# PTI.net
KiCad netlist of a schematic drawn in EAGLE
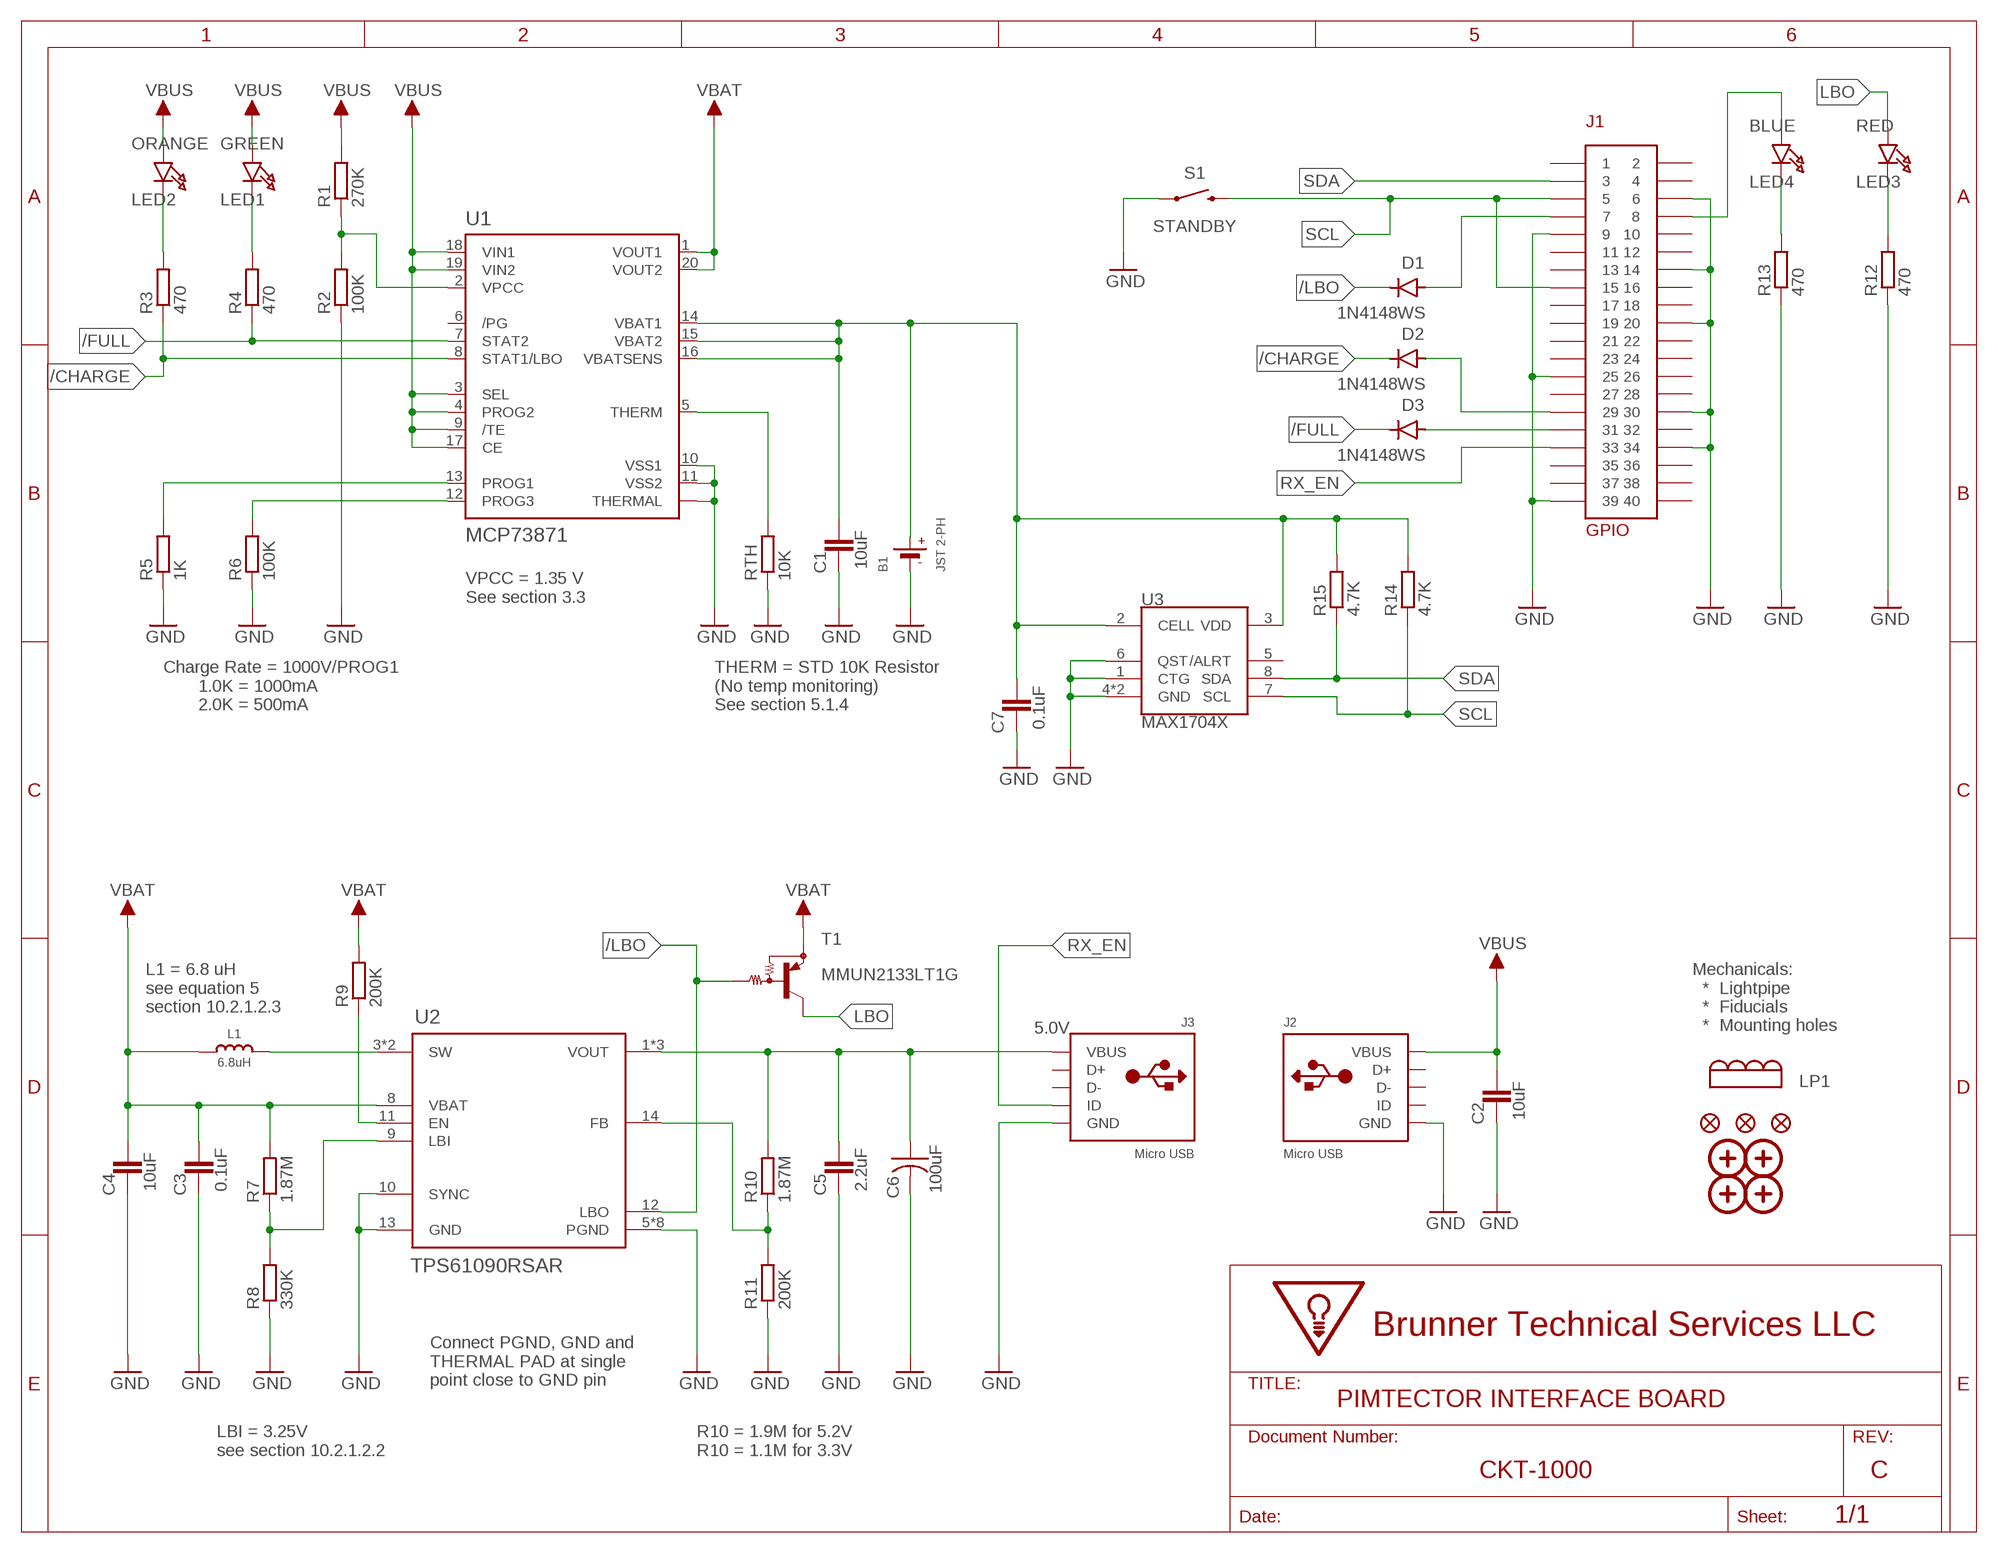
[diagram p0: schematic, sheet 1]

(export (version "E")
  (design (tool "Eeschema 10.0.6"))
  (components
    (comp (ref "B1")
      (value "JST 2-PH")
      (footprint "eagle-import:JSTPH2")
      (libsource (lib "eagle-import") (part "BATTERY"))
    )
    (comp (ref "C1")
      (value "10uF")
      (footprint "eagle-import:C0805")
      (libsource (lib "eagle-import") (part "C-EUC0805"))
    )
    (comp (ref "C2")
      (value "10uF")
      (footprint "eagle-import:C0805")
      (libsource (lib "eagle-import") (part "C-EUC0805"))
    )
    (comp (ref "C3")
      (value "0.1uF")
      (footprint "eagle-import:C0805")
      (libsource (lib "eagle-import") (part "C-EUC0805"))
    )
    (comp (ref "C4")
      (value "10uF")
      (footprint "eagle-import:C0805")
      (libsource (lib "eagle-import") (part "C-EUC0805"))
    )
    (comp (ref "C5")
      (value "2.2uF")
      (footprint "eagle-import:C0805")
      (libsource (lib "eagle-import") (part "C-EUC0805"))
    )
    (comp (ref "C6")
      (value "100uF")
      (footprint "eagle-import:C1210")
      (libsource (lib "eagle-import") (part "C-USC1210"))
    )
    (comp (ref "C7")
      (value "0.1uF")
      (footprint "eagle-import:C0805")
      (libsource (lib "eagle-import") (part "C-EUC0805"))
    )
    (comp (ref "D1")
      (value "1N4148WS")
      (footprint "eagle-import:SOD-323")
      (fields
        (field (name "DIGIKEY_PART_NUMBER") "1N4148WSFSTR-ND")
        (field (name "MANUFACTURER") "Diodes Incorporated")
        (field (name "CREATED_BY") "PCBLayout.com")
      )
      (libsource (lib "eagle-import") (part "1N4148WS"))
    )
    (comp (ref "D2")
      (value "1N4148WS")
      (footprint "eagle-import:SOD-323")
      (fields
        (field (name "DIGIKEY_PART_NUMBER") "1N4148WSFSTR-ND")
        (field (name "MANUFACTURER") "Diodes Incorporated")
        (field (name "CREATED_BY") "PCBLayout.com")
      )
      (libsource (lib "eagle-import") (part "1N4148WS"))
    )
    (comp (ref "D3")
      (value "1N4148WS")
      (footprint "eagle-import:SOD-323")
      (fields
        (field (name "DIGIKEY_PART_NUMBER") "1N4148WSFSTR-ND")
        (field (name "MANUFACTURER") "Diodes Incorporated")
        (field (name "CREATED_BY") "PCBLayout.com")
      )
      (libsource (lib "eagle-import") (part "1N4148WS"))
    )
    (comp (ref "FID1")
      (value "FIDUCIAL\"\"")
      (footprint "eagle-import:FIDUCIAL_1MM")
      (libsource (lib "eagle-import") (part "FIDUCIAL{dblquote}{dblquote}"))
    )
    (comp (ref "FID2")
      (value "FIDUCIAL\"\"")
      (footprint "eagle-import:FIDUCIAL_1MM")
      (libsource (lib "eagle-import") (part "FIDUCIAL{dblquote}{dblquote}"))
    )
    (comp (ref "FID3")
      (value "FIDUCIAL\"\"")
      (footprint "eagle-import:FIDUCIAL_1MM")
      (libsource (lib "eagle-import") (part "FIDUCIAL{dblquote}{dblquote}"))
    )
    (comp (ref "J1")
      (value "GPIO")
      (footprint "eagle-import:HEADER-FE-2X20-TH")
      (libsource (lib "eagle-import") (part "HEADER-FE-2X20THRU-HOLE"))
    )
    (comp (ref "J2")
      (value "Micro USB")
      (footprint "eagle-import:AMPHENOL_10103594")
      (libsource (lib "eagle-import") (part "USB"))
    )
    (comp (ref "J3")
      (value "Micro USB")
      (footprint "eagle-import:AMPHENOL_10103594")
      (libsource (lib "eagle-import") (part "USB"))
    )
    (comp (ref "L1")
      (value "6.8uH")
      (footprint "eagle-import:INDUCTOR_5X5MM_TDK_VLC5045")
      (libsource (lib "eagle-import") (part "INDUCTORTDK_VLC5045"))
    )
    (comp (ref "LED1")
      (value "GREEN")
      (footprint "eagle-import:CHIPLED_0805_NOOUTLINE")
      (libsource (lib "eagle-import") (part "LED0805_NOOUTLINE"))
    )
    (comp (ref "LED2")
      (value "ORANGE")
      (footprint "eagle-import:CHIPLED_0805_NOOUTLINE")
      (libsource (lib "eagle-import") (part "LED0805_NOOUTLINE"))
    )
    (comp (ref "LED3")
      (value "RED")
      (footprint "eagle-import:CHIPLED_0805_NOOUTLINE")
      (libsource (lib "eagle-import") (part "LED0805_NOOUTLINE"))
    )
    (comp (ref "LED4")
      (value "BLUE")
      (footprint "eagle-import:CHIPLED_0805_NOOUTLINE")
      (libsource (lib "eagle-import") (part "LED0805_NOOUTLINE"))
    )
    (comp (ref "LP1")
      (value "LIGHTPIPE")
      (footprint "eagle-import:LIGHTPIPE_QUAD_VERT_3MM")
      (libsource (lib "eagle-import") (part "LIGHTPIPE"))
    )
    (comp (ref "MH1")
      (value "MOUNTING-HOLES")
      (footprint "eagle-import:MOUNTING-HOLE-2.75X3MM")
      (libsource (lib "eagle-import") (part "MOUNTING-HOLES"))
    )
    (comp (ref "MH2")
      (value "MOUNTING-HOLES")
      (footprint "eagle-import:MOUNTING-HOLE-2.75X3MM")
      (libsource (lib "eagle-import") (part "MOUNTING-HOLES"))
    )
    (comp (ref "MH3")
      (value "MOUNTING-HOLES")
      (footprint "eagle-import:MOUNTING-HOLE-2.75X3MM")
      (libsource (lib "eagle-import") (part "MOUNTING-HOLES"))
    )
    (comp (ref "MH4")
      (value "MOUNTING-HOLES")
      (footprint "eagle-import:MOUNTING-HOLE-2.75X3MM")
      (libsource (lib "eagle-import") (part "MOUNTING-HOLES"))
    )
    (comp (ref "R1")
      (value "270K")
      (footprint "eagle-import:R0805")
      (libsource (lib "eagle-import") (part "R-EU_R0805"))
    )
    (comp (ref "R2")
      (value "100K")
      (footprint "eagle-import:R0805")
      (libsource (lib "eagle-import") (part "R-EU_R0805"))
    )
    (comp (ref "R3")
      (value "470")
      (footprint "eagle-import:R0805")
      (libsource (lib "eagle-import") (part "R-EU_R0805"))
    )
    (comp (ref "R4")
      (value "470")
      (footprint "eagle-import:R0805")
      (libsource (lib "eagle-import") (part "R-EU_R0805"))
    )
    (comp (ref "R5")
      (value "1K")
      (footprint "eagle-import:R0805")
      (libsource (lib "eagle-import") (part "R-EU_R0805"))
    )
    (comp (ref "R6")
      (value "100K")
      (footprint "eagle-import:R0805")
      (libsource (lib "eagle-import") (part "R-EU_R0805"))
    )
    (comp (ref "R7")
      (value "1.87M")
      (footprint "eagle-import:R0805")
      (libsource (lib "eagle-import") (part "R-EU_R0805"))
    )
    (comp (ref "R8")
      (value "330K")
      (footprint "eagle-import:R0805")
      (libsource (lib "eagle-import") (part "R-EU_R0805"))
    )
    (comp (ref "R9")
      (value "200K")
      (footprint "eagle-import:R0805")
      (libsource (lib "eagle-import") (part "R-EU_R0805"))
    )
    (comp (ref "R10")
      (value "1.87M")
      (footprint "eagle-import:R0805")
      (libsource (lib "eagle-import") (part "R-EU_R0805"))
    )
    (comp (ref "R11")
      (value "200K")
      (footprint "eagle-import:R0805")
      (libsource (lib "eagle-import") (part "R-EU_R0805"))
    )
    (comp (ref "R12")
      (value "470")
      (footprint "eagle-import:R0805")
      (libsource (lib "eagle-import") (part "R-EU_R0805"))
    )
    (comp (ref "R13")
      (value "470")
      (footprint "eagle-import:R0805")
      (libsource (lib "eagle-import") (part "R-EU_R0805"))
    )
    (comp (ref "R14")
      (value "4.7K")
      (footprint "eagle-import:R0805")
      (libsource (lib "eagle-import") (part "R-EU_R0805"))
    )
    (comp (ref "R15")
      (value "4.7K")
      (footprint "eagle-import:R0805")
      (libsource (lib "eagle-import") (part "R-EU_R0805"))
    )
    (comp (ref "RTH")
      (value "10K")
      (footprint "eagle-import:R0805")
      (libsource (lib "eagle-import") (part "R-EU_R0805"))
    )
    (comp (ref "S1")
      (value "STANDBY")
      (footprint "eagle-import:TACTILE_SWITCH_PTH_12MM")
      (libsource (lib "eagle-import") (part "MOMENTARY-SWITCH-SPST-PTH-12MM"))
    )
    (comp (ref "T1")
      (value "MMUN2133LT1G")
      (footprint "eagle-import:SC59-BEC")
      (libsource (lib "eagle-import") (part "-PNP_DRIVER-SC59-BECMUN2111T1"))
    )
    (comp (ref "U1")
      (value "MCP73871")
      (footprint "eagle-import:QFN20_4MM")
      (libsource (lib "eagle-import") (part "MCP73871"))
    )
    (comp (ref "U2")
      (value "TPS61090RSAR")
      (footprint "eagle-import:RSA16_4MMX4MM_VQFN")
      (fields (field (name "MANUFACTURER") "TI"))
      (libsource (lib "eagle-import") (part "TPS6109X"))
    )
    (comp (ref "U3")
      (value "MAX1704X")
      (footprint "eagle-import:TDFN-8")
      (libsource (lib "eagle-import") (part "MAX1704X"))
    )
  )
  (nets
    (net (code "1") (name "/5.0V") (class "Default")
      (node (ref "C5") (pin "1") (pinfunction "1_1") (pintype "passive"))
      (node (ref "C6") (pin "1") (pinfunction "1_1") (pintype "passive"))
      (node (ref "J3") (pin "VBUS") (pinfunction "VBUS_VBUS") (pintype "power_in"))
      (node (ref "R10") (pin "2") (pinfunction "2_2") (pintype "passive"))
      (node (ref "U2") (pin "1") (pinfunction "VOUT_1") (pintype "output"))
      (node (ref "U2") (pin "15") (pinfunction "VOUT_15") (pintype "output"))
      (node (ref "U2") (pin "16") (pinfunction "VOUT_16") (pintype "output"))
    )
    (net (code "2") (name "GND") (class "Default")
      (node (ref "B1") (pin "1") (pinfunction "-_1") (pintype "passive"))
      (node (ref "B1") (pin "NC1") (pinfunction "-_NC1") (pintype "passive"))
      (node (ref "B1") (pin "NC2") (pinfunction "-_NC2") (pintype "passive"))
      (node (ref "C1") (pin "2") (pinfunction "2_2") (pintype "passive"))
      (node (ref "C2") (pin "2") (pinfunction "2_2") (pintype "passive"))
      (node (ref "C3") (pin "2") (pinfunction "2_2") (pintype "passive"))
      (node (ref "C4") (pin "2") (pinfunction "2_2") (pintype "passive"))
      (node (ref "C5") (pin "2") (pinfunction "2_2") (pintype "passive"))
      (node (ref "C6") (pin "2") (pinfunction "2_2") (pintype "passive"))
      (node (ref "C7") (pin "2") (pinfunction "2_2") (pintype "passive"))
      (node (ref "J1") (pin "P$14") (pinfunction "14_P$14") (pintype "bidirectional"))
      (node (ref "J1") (pin "P$20") (pinfunction "20_P$20") (pintype "bidirectional"))
      (node (ref "J1") (pin "P$25") (pinfunction "25_P$25") (pintype "bidirectional"))
      (node (ref "J1") (pin "P$30") (pinfunction "30_P$30") (pintype "bidirectional"))
      (node (ref "J1") (pin "P$34") (pinfunction "34_P$34") (pintype "bidirectional"))
      (node (ref "J1") (pin "P$39") (pinfunction "39_P$39") (pintype "bidirectional"))
      (node (ref "J1") (pin "P$6") (pinfunction "6_P$6") (pintype "bidirectional"))
      (node (ref "J1") (pin "P$9") (pinfunction "9_P$9") (pintype "bidirectional"))
      (node (ref "J2") (pin "BASE@1") (pinfunction "GND_BASE@1") (pintype "power_in"))
      (node (ref "J2") (pin "BASE@2") (pinfunction "GND_BASE@2") (pintype "power_in"))
      (node (ref "J2") (pin "GND") (pinfunction "GND_GND") (pintype "power_in"))
      (node (ref "J2") (pin "SPRT@1") (pinfunction "GND_SPRT@1") (pintype "power_in"))
      (node (ref "J2") (pin "SPRT@2") (pinfunction "GND_SPRT@2") (pintype "power_in"))
      (node (ref "J2") (pin "SPRT@3") (pinfunction "GND_SPRT@3") (pintype "power_in"))
      (node (ref "J2") (pin "SPRT@4") (pinfunction "GND_SPRT@4") (pintype "power_in"))
      (node (ref "J3") (pin "BASE@1") (pinfunction "GND_BASE@1") (pintype "power_in"))
      (node (ref "J3") (pin "BASE@2") (pinfunction "GND_BASE@2") (pintype "power_in"))
      (node (ref "J3") (pin "GND") (pinfunction "GND_GND") (pintype "power_in"))
      (node (ref "J3") (pin "SPRT@1") (pinfunction "GND_SPRT@1") (pintype "power_in"))
      (node (ref "J3") (pin "SPRT@2") (pinfunction "GND_SPRT@2") (pintype "power_in"))
      (node (ref "J3") (pin "SPRT@3") (pinfunction "GND_SPRT@3") (pintype "power_in"))
      (node (ref "J3") (pin "SPRT@4") (pinfunction "GND_SPRT@4") (pintype "power_in"))
      (node (ref "R11") (pin "1") (pinfunction "1_1") (pintype "passive"))
      (node (ref "R12") (pin "1") (pinfunction "1_1") (pintype "passive"))
      (node (ref "R13") (pin "1") (pinfunction "1_1") (pintype "passive"))
      (node (ref "R2") (pin "1") (pinfunction "1_1") (pintype "passive"))
      (node (ref "R5") (pin "1") (pinfunction "1_1") (pintype "passive"))
      (node (ref "R6") (pin "1") (pinfunction "1_1") (pintype "passive"))
      (node (ref "R8") (pin "1") (pinfunction "1_1") (pintype "passive"))
      (node (ref "RTH") (pin "1") (pinfunction "1_1") (pintype "passive"))
      (node (ref "S1") (pin "1") (pinfunction "1_1") (pintype "passive"))
      (node (ref "U1") (pin "10") (pinfunction "VSS1_10") (pintype "bidirectional"))
      (node (ref "U1") (pin "11") (pinfunction "VSS2_11") (pintype "bidirectional"))
      (node (ref "U1") (pin "P$21") (pinfunction "THERMAL_P$21") (pintype "bidirectional"))
      (node (ref "U1") (pin "P$22") (pinfunction "THERMAL_P$22") (pintype "bidirectional"))
      (node (ref "U1") (pin "P$23") (pinfunction "THERMAL_P$23") (pintype "bidirectional"))
      (node (ref "U1") (pin "P$24") (pinfunction "THERMAL_P$24") (pintype "bidirectional"))
      (node (ref "U2") (pin "10") (pinfunction "SYNC_10") (pintype "input"))
      (node (ref "U2") (pin "13") (pinfunction "GND_13") (pintype "power_in"))
      (node (ref "U2") (pin "5") (pinfunction "PGND_5") (pintype "bidirectional"))
      (node (ref "U2") (pin "6") (pinfunction "PGND_6") (pintype "bidirectional"))
      (node (ref "U2") (pin "7") (pinfunction "PGND_7") (pintype "bidirectional"))
      (node (ref "U2") (pin "P$17") (pinfunction "PGND_P$17") (pintype "bidirectional"))
      (node (ref "U2") (pin "P$18") (pinfunction "PGND_P$18") (pintype "bidirectional"))
      (node (ref "U2") (pin "P$19") (pinfunction "PGND_P$19") (pintype "bidirectional"))
      (node (ref "U2") (pin "P$20") (pinfunction "PGND_P$20") (pintype "bidirectional"))
      (node (ref "U2") (pin "P$21") (pinfunction "PGND_P$21") (pintype "bidirectional"))
      (node (ref "U3") (pin "1") (pinfunction "CTG_1") (pintype "bidirectional"))
      (node (ref "U3") (pin "4") (pinfunction "GND_4") (pintype "bidirectional"))
      (node (ref "U3") (pin "6") (pinfunction "QST_6") (pintype "bidirectional"))
      (node (ref "U3") (pin "EP") (pinfunction "GND_EP") (pintype "bidirectional"))
    )
    (net (code "3") (name "LBO") (class "Default")
      (node (ref "LED3") (pin "A") (pinfunction "A_A") (pintype "passive"))
      (node (ref "T1") (pin "C") (pinfunction "C_C") (pintype "passive"))
    )
    (net (code "4") (name "Net-(B1-+)") (class "Default")
      (node (ref "B1") (pin "2") (pinfunction "+_2") (pintype "passive"))
      (node (ref "C1") (pin "1") (pinfunction "1_1") (pintype "passive"))
      (node (ref "C7") (pin "1") (pinfunction "1_1") (pintype "passive"))
      (node (ref "R14") (pin "2") (pinfunction "2_2") (pintype "passive"))
      (node (ref "R15") (pin "2") (pinfunction "2_2") (pintype "passive"))
      (node (ref "U1") (pin "14") (pinfunction "VBAT1_14") (pintype "bidirectional"))
      (node (ref "U1") (pin "15") (pinfunction "VBAT2_15") (pintype "bidirectional"))
      (node (ref "U1") (pin "16") (pinfunction "VBATSENS_16") (pintype "bidirectional"))
      (node (ref "U3") (pin "2") (pinfunction "CELL_2") (pintype "bidirectional"))
      (node (ref "U3") (pin "3") (pinfunction "VDD_3") (pintype "bidirectional"))
    )
    (net (code "5") (name "Net-(J1-7)") (class "Default")
      (node (ref "D1") (pin "A") (pinfunction "A_A") (pintype "passive"))
      (node (ref "J1") (pin "P$7") (pinfunction "7_P$7") (pintype "bidirectional"))
    )
    (net (code "6") (name "Net-(J1-8)") (class "Default")
      (node (ref "J1") (pin "P$8") (pinfunction "8_P$8") (pintype "bidirectional"))
      (node (ref "LED4") (pin "A") (pinfunction "A_A") (pintype "passive"))
    )
    (net (code "7") (name "Net-(J1-29)") (class "Default")
      (node (ref "D2") (pin "A") (pinfunction "A_A") (pintype "passive"))
      (node (ref "J1") (pin "P$29") (pinfunction "29_P$29") (pintype "bidirectional"))
    )
    (net (code "8") (name "Net-(J1-31)") (class "Default")
      (node (ref "D3") (pin "A") (pinfunction "A_A") (pintype "passive"))
      (node (ref "J1") (pin "P$31") (pinfunction "31_P$31") (pintype "bidirectional"))
    )
    (net (code "9") (name "Net-(L1-2)") (class "Default")
      (node (ref "L1") (pin "P$2") (pinfunction "2_P$2") (pintype "passive"))
      (node (ref "U2") (pin "3") (pinfunction "SW_3") (pintype "input"))
      (node (ref "U2") (pin "4") (pinfunction "SW_4") (pintype "input"))
    )
    (net (code "10") (name "Net-(LED1-PadC)") (class "Default")
      (node (ref "LED1") (pin "C") (pinfunction "C_C") (pintype "passive"))
      (node (ref "R4") (pin "2") (pinfunction "2_2") (pintype "passive"))
    )
    (net (code "11") (name "Net-(LED2-PadC)") (class "Default")
      (node (ref "LED2") (pin "C") (pinfunction "C_C") (pintype "passive"))
      (node (ref "R3") (pin "2") (pinfunction "2_2") (pintype "passive"))
    )
    (net (code "12") (name "Net-(LED3-PadC)") (class "Default")
      (node (ref "LED3") (pin "C") (pinfunction "C_C") (pintype "passive"))
      (node (ref "R12") (pin "2") (pinfunction "2_2") (pintype "passive"))
    )
    (net (code "13") (name "Net-(LED4-PadC)") (class "Default")
      (node (ref "LED4") (pin "C") (pinfunction "C_C") (pintype "passive"))
      (node (ref "R13") (pin "2") (pinfunction "2_2") (pintype "passive"))
    )
    (net (code "14") (name "Net-(U1-PROG1)") (class "Default")
      (node (ref "R5") (pin "2") (pinfunction "2_2") (pintype "passive"))
      (node (ref "U1") (pin "13") (pinfunction "PROG1_13") (pintype "bidirectional"))
    )
    (net (code "15") (name "Net-(U1-PROG3)") (class "Default")
      (node (ref "R6") (pin "2") (pinfunction "2_2") (pintype "passive"))
      (node (ref "U1") (pin "12") (pinfunction "PROG3_12") (pintype "bidirectional"))
    )
    (net (code "16") (name "Net-(U1-THERM)") (class "Default")
      (node (ref "RTH") (pin "2") (pinfunction "2_2") (pintype "passive"))
      (node (ref "U1") (pin "5") (pinfunction "THERM_5") (pintype "bidirectional"))
    )
    (net (code "17") (name "Net-(U1-VPCC)") (class "Default")
      (node (ref "R1") (pin "1") (pinfunction "1_1") (pintype "passive"))
      (node (ref "R2") (pin "2") (pinfunction "2_2") (pintype "passive"))
      (node (ref "U1") (pin "2") (pinfunction "VPCC_2") (pintype "bidirectional"))
    )
    (net (code "18") (name "Net-(U2-EN)") (class "Default")
      (node (ref "R9") (pin "1") (pinfunction "1_1") (pintype "passive"))
      (node (ref "U2") (pin "11") (pinfunction "EN_11") (pintype "input"))
    )
    (net (code "19") (name "Net-(U2-FB)") (class "Default")
      (node (ref "R10") (pin "1") (pinfunction "1_1") (pintype "passive"))
      (node (ref "R11") (pin "2") (pinfunction "2_2") (pintype "passive"))
      (node (ref "U2") (pin "14") (pinfunction "FB_14") (pintype "input"))
    )
    (net (code "20") (name "Net-(U2-LBI)") (class "Default")
      (node (ref "R7") (pin "1") (pinfunction "1_1") (pintype "passive"))
      (node (ref "R8") (pin "2") (pinfunction "2_2") (pintype "passive"))
      (node (ref "U2") (pin "9") (pinfunction "LBI_9") (pintype "input"))
    )
    (net (code "21") (name "RX_EN") (class "Default")
      (node (ref "J1") (pin "P$33") (pinfunction "33_P$33") (pintype "bidirectional"))
      (node (ref "J3") (pin "ID") (pinfunction "ID_ID") (pintype "bidirectional"))
    )
    (net (code "22") (name "SCL") (class "Default")
      (node (ref "J1") (pin "P$15") (pinfunction "15_P$15") (pintype "bidirectional"))
      (node (ref "J1") (pin "P$5") (pinfunction "5_P$5") (pintype "bidirectional"))
      (node (ref "R14") (pin "1") (pinfunction "1_1") (pintype "passive"))
      (node (ref "S1") (pin "3") (pinfunction "2_3") (pintype "passive"))
      (node (ref "U3") (pin "7") (pinfunction "SCL_7") (pintype "bidirectional"))
    )
    (net (code "23") (name "SDA") (class "Default")
      (node (ref "J1") (pin "P$3") (pinfunction "3_P$3") (pintype "bidirectional"))
      (node (ref "R15") (pin "1") (pinfunction "1_1") (pintype "passive"))
      (node (ref "U3") (pin "8") (pinfunction "SDA_8") (pintype "bidirectional"))
    )
    (net (code "24") (name "VBAT") (class "Default")
      (node (ref "C3") (pin "1") (pinfunction "1_1") (pintype "passive"))
      (node (ref "C4") (pin "1") (pinfunction "1_1") (pintype "passive"))
      (node (ref "L1") (pin "P$1") (pinfunction "1_P$1") (pintype "passive"))
      (node (ref "R7") (pin "2") (pinfunction "2_2") (pintype "passive"))
      (node (ref "R9") (pin "2") (pinfunction "2_2") (pintype "passive"))
      (node (ref "T1") (pin "E") (pinfunction "E_E") (pintype "passive"))
      (node (ref "U1") (pin "1") (pinfunction "VOUT1_1") (pintype "bidirectional"))
      (node (ref "U1") (pin "20") (pinfunction "VOUT2_20") (pintype "bidirectional"))
      (node (ref "U2") (pin "8") (pinfunction "VBAT_8") (pintype "input"))
    )
    (net (code "25") (name "VBUS") (class "Default")
      (node (ref "C2") (pin "1") (pinfunction "1_1") (pintype "passive"))
      (node (ref "J2") (pin "VBUS") (pinfunction "VBUS_VBUS") (pintype "power_in"))
      (node (ref "LED1") (pin "A") (pinfunction "A_A") (pintype "passive"))
      (node (ref "LED2") (pin "A") (pinfunction "A_A") (pintype "passive"))
      (node (ref "R1") (pin "2") (pinfunction "2_2") (pintype "passive"))
      (node (ref "U1") (pin "17") (pinfunction "CE_17") (pintype "bidirectional"))
      (node (ref "U1") (pin "18") (pinfunction "VIN1_18") (pintype "bidirectional"))
      (node (ref "U1") (pin "19") (pinfunction "VIN2_19") (pintype "bidirectional"))
      (node (ref "U1") (pin "3") (pinfunction "SEL_3") (pintype "bidirectional"))
      (node (ref "U1") (pin "4") (pinfunction "PROG2_4") (pintype "bidirectional"))
      (node (ref "U1") (pin "9") (pinfunction "/TE_9") (pintype "bidirectional"))
    )
    (net (code "26") (name "unconnected-(J1-1-PadP$1)") (class "Default")
      (node (ref "J1") (pin "P$1") (pinfunction "1_P$1") (pintype "bidirectional"))
    )
    (net (code "27") (name "unconnected-(J1-2-PadP$2)") (class "Default")
      (node (ref "J1") (pin "P$2") (pinfunction "2_P$2") (pintype "bidirectional"))
    )
    (net (code "28") (name "unconnected-(J1-4-PadP$4)") (class "Default")
      (node (ref "J1") (pin "P$4") (pinfunction "4_P$4") (pintype "bidirectional"))
    )
    (net (code "29") (name "unconnected-(J1-10-PadP$10)") (class "Default")
      (node (ref "J1") (pin "P$10") (pinfunction "10_P$10") (pintype "bidirectional"))
    )
    (net (code "30") (name "unconnected-(J1-11-PadP$11)") (class "Default")
      (node (ref "J1") (pin "P$11") (pinfunction "11_P$11") (pintype "bidirectional"))
    )
    (net (code "31") (name "unconnected-(J1-12-PadP$12)") (class "Default")
      (node (ref "J1") (pin "P$12") (pinfunction "12_P$12") (pintype "bidirectional"))
    )
    (net (code "32") (name "unconnected-(J1-13-PadP$13)") (class "Default")
      (node (ref "J1") (pin "P$13") (pinfunction "13_P$13") (pintype "bidirectional"))
    )
    (net (code "33") (name "unconnected-(J1-16-PadP$16)") (class "Default")
      (node (ref "J1") (pin "P$16") (pinfunction "16_P$16") (pintype "bidirectional"))
    )
    (net (code "34") (name "unconnected-(J1-17-PadP$17)") (class "Default")
      (node (ref "J1") (pin "P$17") (pinfunction "17_P$17") (pintype "bidirectional"))
    )
    (net (code "35") (name "unconnected-(J1-18-PadP$18)") (class "Default")
      (node (ref "J1") (pin "P$18") (pinfunction "18_P$18") (pintype "bidirectional"))
    )
    (net (code "36") (name "unconnected-(J1-19-PadP$19)") (class "Default")
      (node (ref "J1") (pin "P$19") (pinfunction "19_P$19") (pintype "bidirectional"))
    )
    (net (code "37") (name "unconnected-(J1-21-PadP$21)") (class "Default")
      (node (ref "J1") (pin "P$21") (pinfunction "21_P$21") (pintype "bidirectional"))
    )
    (net (code "38") (name "unconnected-(J1-22-PadP$22)") (class "Default")
      (node (ref "J1") (pin "P$22") (pinfunction "22_P$22") (pintype "bidirectional"))
    )
    (net (code "39") (name "unconnected-(J1-23-PadP$23)") (class "Default")
      (node (ref "J1") (pin "P$23") (pinfunction "23_P$23") (pintype "bidirectional"))
    )
    (net (code "40") (name "unconnected-(J1-24-PadP$24)") (class "Default")
      (node (ref "J1") (pin "P$24") (pinfunction "24_P$24") (pintype "bidirectional"))
    )
    (net (code "41") (name "unconnected-(J1-26-PadP$26)") (class "Default")
      (node (ref "J1") (pin "P$26") (pinfunction "26_P$26") (pintype "bidirectional"))
    )
    (net (code "42") (name "unconnected-(J1-27-PadP$27)") (class "Default")
      (node (ref "J1") (pin "P$27") (pinfunction "27_P$27") (pintype "bidirectional"))
    )
    (net (code "43") (name "unconnected-(J1-28-PadP$28)") (class "Default")
      (node (ref "J1") (pin "P$28") (pinfunction "28_P$28") (pintype "bidirectional"))
    )
    (net (code "44") (name "unconnected-(J1-32-PadP$32)") (class "Default")
      (node (ref "J1") (pin "P$32") (pinfunction "32_P$32") (pintype "bidirectional"))
    )
    (net (code "45") (name "unconnected-(J1-35-PadP$35)") (class "Default")
      (node (ref "J1") (pin "P$35") (pinfunction "35_P$35") (pintype "bidirectional"))
    )
    (net (code "46") (name "unconnected-(J1-36-PadP$36)") (class "Default")
      (node (ref "J1") (pin "P$36") (pinfunction "36_P$36") (pintype "bidirectional"))
    )
    (net (code "47") (name "unconnected-(J1-37-PadP$37)") (class "Default")
      (node (ref "J1") (pin "P$37") (pinfunction "37_P$37") (pintype "bidirectional"))
    )
    (net (code "48") (name "unconnected-(J1-38-PadP$38)") (class "Default")
      (node (ref "J1") (pin "P$38") (pinfunction "38_P$38") (pintype "bidirectional"))
    )
    (net (code "49") (name "unconnected-(J1-40-PadP$40)") (class "Default")
      (node (ref "J1") (pin "P$40") (pinfunction "40_P$40") (pintype "bidirectional"))
    )
    (net (code "50") (name "unconnected-(J2-PadD+)") (class "Default")
      (node (ref "J2") (pin "D+") (pinfunction "D+_D+") (pintype "bidirectional"))
    )
    (net (code "51") (name "unconnected-(J2-PadD-)") (class "Default")
      (node (ref "J2") (pin "D-") (pinfunction "D-_D-") (pintype "bidirectional"))
    )
    (net (code "52") (name "unconnected-(J2-PadID)") (class "Default")
      (node (ref "J2") (pin "ID") (pinfunction "ID_ID") (pintype "bidirectional"))
    )
    (net (code "53") (name "unconnected-(J3-PadD+)") (class "Default")
      (node (ref "J3") (pin "D+") (pinfunction "D+_D+") (pintype "bidirectional"))
    )
    (net (code "54") (name "unconnected-(J3-PadD-)") (class "Default")
      (node (ref "J3") (pin "D-") (pinfunction "D-_D-") (pintype "bidirectional"))
    )
    (net (code "55") (name "unconnected-(U1-{slash}PG-Pad6)") (class "Default")
      (node (ref "U1") (pin "6") (pinfunction "/PG_6") (pintype "bidirectional"))
    )
    (net (code "56") (name "unconnected-(U3-{slash}ALRT-Pad5)") (class "Default")
      (node (ref "U3") (pin "5") (pinfunction "/ALRT_5") (pintype "bidirectional"))
    )
    (net (code "57") (name "{slash}CHARGE") (class "Default")
      (node (ref "D2") (pin "C") (pinfunction "C_C") (pintype "passive"))
      (node (ref "R3") (pin "1") (pinfunction "1_1") (pintype "passive"))
      (node (ref "U1") (pin "8") (pinfunction "STAT1/LBO_8") (pintype "bidirectional"))
    )
    (net (code "58") (name "{slash}FULL") (class "Default")
      (node (ref "D3") (pin "C") (pinfunction "C_C") (pintype "passive"))
      (node (ref "R4") (pin "1") (pinfunction "1_1") (pintype "passive"))
      (node (ref "U1") (pin "7") (pinfunction "STAT2_7") (pintype "bidirectional"))
    )
    (net (code "59") (name "{slash}LBO") (class "Default")
      (node (ref "D1") (pin "C") (pinfunction "C_C") (pintype "passive"))
      (node (ref "T1") (pin "B") (pinfunction "B_B") (pintype "passive"))
      (node (ref "U2") (pin "12") (pinfunction "LBO_12") (pintype "output"))
    )
  )
)
